# 04_Sensor.net
KiCad netlist of a schematic drawn in Altium Designer
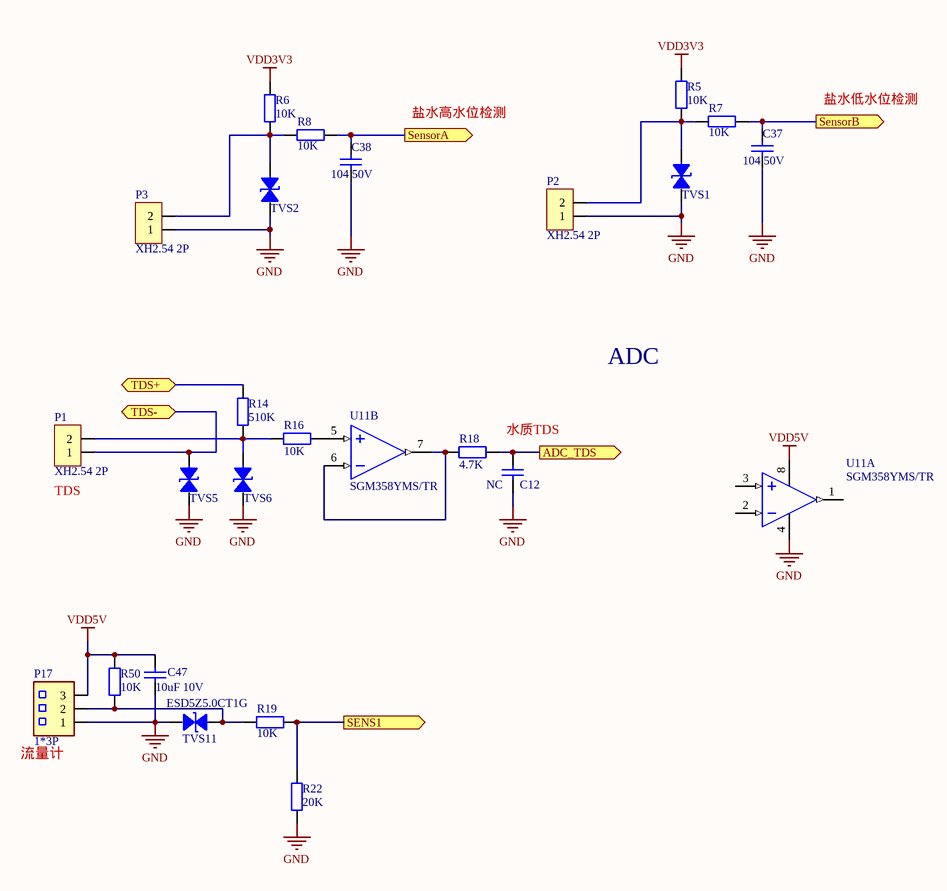
[diagram p0: 04_Sensor.SchDoc]

(export (version "E")
  (design (tool "Eeschema 10.0.6"))
  (components
    (comp (ref "C12")
      (value "NC")
      (footprint "SMD-0603C")
      (description "贴片电容 10%")
      (libsource (lib "XiaoyI") (part "CAP4"))
    )
    (comp (ref "C37")
      (value "104 50V")
      (footprint "SMD-0603C")
      (description "贴片电容 20%")
      (libsource (lib "XiaoyI") (part "CAP4"))
    )
    (comp (ref "C38")
      (value "104 50V")
      (footprint "SMD-0603C")
      (description "贴片电容 20%")
      (libsource (lib "XiaoyI") (part "CAP4"))
    )
    (comp (ref "C47")
      (value "10uF 10V")
      (footprint "SMD-0603C")
      (description "贴片电容 10%")
      (libsource (lib "Miscellaneous Devices LC") (part "0805 22uF (226) 20% 25V"))
    )
    (comp (ref "P1")
      (value "XH2.54 2P")
      (footprint "SIP-2A")
      (description "XH2.54 2P 直插")
      (libsource (lib "XiaoyI") (part "SIP-2"))
    )
    (comp (ref "P2")
      (value "XH2.54 2P")
      (footprint "SIP-2A")
      (description "XH2.54 2P 直插")
      (libsource (lib "XiaoyI") (part "SIP-2"))
    )
    (comp (ref "P3")
      (value "XH2.54 2P")
      (footprint "SIP-2A")
      (description "XH2.54 2P 直插")
      (libsource (lib "XiaoyI") (part "SIP-2"))
    )
    (comp (ref "P17")
      (value "1*3P")
      (footprint "3X2.54MMZ2")
      (libsource (lib "PARK-N5 V1.0") (part "HDR1*3"))
    )
    (comp (ref "R5")
      (value "10K")
      (footprint "SMD-0603")
      (description "贴片电阻 1%")
      (libsource (lib "ABB") (part "RES0"))
    )
    (comp (ref "R6")
      (value "10K")
      (footprint "SMD-0603")
      (description "贴片电阻 1%")
      (libsource (lib "ABB") (part "RES0"))
    )
    (comp (ref "R7")
      (value "10K")
      (footprint "SMD-0603")
      (description "贴片电阻 1%")
      (libsource (lib "") (part "RES0_2"))
    )
    (comp (ref "R8")
      (value "10K")
      (footprint "SMD-0603")
      (description "贴片电阻 1%")
      (libsource (lib "") (part "RES0_2"))
    )
    (comp (ref "R14")
      (value "510K")
      (footprint "SMD-0603")
      (description "贴片电阻 1%")
      (libsource (lib "ABB") (part "RES0"))
    )
    (comp (ref "R16")
      (value "10K")
      (footprint "SMD-0603")
      (description "贴片电阻 1%")
      (libsource (lib "") (part "RES0_2"))
    )
    (comp (ref "R18")
      (value "4.7K")
      (footprint "SMD-0603")
      (description "贴片电阻 5%")
      (libsource (lib "") (part "RES0_1"))
    )
    (comp (ref "R19")
      (value "10K")
      (footprint "SMD-0603")
      (description "贴片电阻 5%")
      (libsource (lib "Miscellaneous Devices LC") (part "0603 10KΩ (1002) 1%"))
    )
    (comp (ref "R22")
      (value "20K")
      (footprint "SMD-0603")
      (description "贴片电阻 5%")
      (libsource (lib "") (part "0603 10KΩ (1002) 1%_2"))
    )
    (comp (ref "R50")
      (value "10K")
      (footprint "SMD-0603")
      (description "贴片电阻 5%")
      (libsource (lib "") (part "0603 10KΩ (1002) 1%_1"))
    )
    (comp (ref "TVS1")
      (value "ESD5Z5.0CT1G")
      (footprint "SOD-523")
      (description "TVS")
      (libsource (lib "XiaoyI") (part "TVS-1"))
    )
    (comp (ref "TVS2")
      (value "ESD5Z5.0CT1G")
      (footprint "SOD-523")
      (description "TVS")
      (libsource (lib "XiaoyI") (part "TVS-1"))
    )
    (comp (ref "TVS5")
      (value "ESD5Z5.0CT1G")
      (footprint "SOD-523")
      (description "TVS")
      (libsource (lib "XiaoyI") (part "TVS-1"))
    )
    (comp (ref "TVS6")
      (value "ESD5Z5.0CT1G")
      (footprint "SOD-523")
      (description "TVS")
      (libsource (lib "XiaoyI") (part "TVS-1"))
    )
    (comp (ref "TVS11")
      (value "ESD5Z5.0CT1G")
      (footprint "SOD-523")
      (description "TVS 5.0V")
      (libsource (lib "XiaoyI") (part "TVS-1"))
    )
    (comp (ref "U11")
      (value "SGM358YMS/TR")
      (footprint "MSOP-8")
      (description "运放")
      (libsource (lib "XiaoyI") (part "LM358"))
    )
  )
  (nets
    (net (code "1") (name "/ADC_TDS") (class "Default")
      (node (ref "C12") (pin "2") (pinfunction "2_2") (pintype "passive"))
      (node (ref "R18") (pin "1") (pinfunction "1_1") (pintype "passive"))
    )
    (net (code "2") (name "/SENS1") (class "Default")
      (node (ref "R19") (pin "2") (pinfunction "2_2") (pintype "passive"))
      (node (ref "R22") (pin "2") (pinfunction "2_2") (pintype "passive"))
    )
    (net (code "3") (name "/SensorA") (class "Default")
      (node (ref "C38") (pin "2") (pinfunction "2_2") (pintype "passive"))
      (node (ref "R8") (pin "2") (pinfunction "2_2") (pintype "passive"))
    )
    (net (code "4") (name "/SensorB") (class "Default")
      (node (ref "C37") (pin "2") (pinfunction "2_2") (pintype "passive"))
      (node (ref "R7") (pin "2") (pinfunction "2_2") (pintype "passive"))
    )
    (net (code "5") (name "/TDS+") (class "Default")
      (node (ref "R14") (pin "1") (pinfunction "1_1") (pintype "passive"))
    )
    (net (code "6") (name "/TDS-") (class "Default")
      (node (ref "P1") (pin "1") (pinfunction "1_1") (pintype "passive"))
      (node (ref "TVS5") (pin "2") (pinfunction "B_2") (pintype "passive"))
    )
    (net (code "7") (name "GND") (class "Default")
      (node (ref "C12") (pin "1") (pinfunction "1_1") (pintype "passive"))
      (node (ref "C37") (pin "1") (pinfunction "1_1") (pintype "passive"))
      (node (ref "C38") (pin "1") (pinfunction "1_1") (pintype "passive"))
      (node (ref "C47") (pin "1") (pinfunction "1_1") (pintype "passive"))
      (node (ref "P17") (pin "1") (pinfunction "1_1") (pintype "passive"))
      (node (ref "P2") (pin "1") (pinfunction "1_1") (pintype "passive"))
      (node (ref "P3") (pin "1") (pinfunction "1_1") (pintype "passive"))
      (node (ref "R22") (pin "1") (pinfunction "1_1") (pintype "passive"))
      (node (ref "TVS1") (pin "1") (pinfunction "A_1") (pintype "passive"))
      (node (ref "TVS11") (pin "1") (pinfunction "A_1") (pintype "passive"))
      (node (ref "TVS2") (pin "1") (pinfunction "A_1") (pintype "passive"))
      (node (ref "TVS5") (pin "1") (pinfunction "A_1") (pintype "passive"))
      (node (ref "TVS6") (pin "1") (pinfunction "A_1") (pintype "passive"))
      (node (ref "U11") (pin "4") (pinfunction "V-_4") (pintype "power_in"))
    )
    (net (code "8") (name "Net-(TVS1-B)") (class "Default")
      (node (ref "P2") (pin "2") (pinfunction "2_2") (pintype "passive"))
      (node (ref "R5") (pin "2") (pinfunction "2_2") (pintype "passive"))
      (node (ref "R7") (pin "1") (pinfunction "1_1") (pintype "passive"))
      (node (ref "TVS1") (pin "2") (pinfunction "B_2") (pintype "passive"))
    )
    (net (code "9") (name "Net-(TVS2-B)") (class "Default")
      (node (ref "P3") (pin "2") (pinfunction "2_2") (pintype "passive"))
      (node (ref "R6") (pin "2") (pinfunction "2_2") (pintype "passive"))
      (node (ref "R8") (pin "1") (pinfunction "1_1") (pintype "passive"))
      (node (ref "TVS2") (pin "2") (pinfunction "B_2") (pintype "passive"))
    )
    (net (code "10") (name "Net-(TVS6-B)") (class "Default")
      (node (ref "P1") (pin "2") (pinfunction "2_2") (pintype "passive"))
      (node (ref "R14") (pin "2") (pinfunction "2_2") (pintype "passive"))
      (node (ref "R16") (pin "1") (pinfunction "1_1") (pintype "passive"))
      (node (ref "TVS6") (pin "2") (pinfunction "B_2") (pintype "passive"))
    )
    (net (code "11") (name "Net-(TVS11-B)") (class "Default")
      (node (ref "P17") (pin "2") (pinfunction "2_2") (pintype "passive"))
      (node (ref "R19") (pin "1") (pinfunction "1_1") (pintype "passive"))
      (node (ref "R50") (pin "2") (pinfunction "2_2") (pintype "passive"))
      (node (ref "TVS11") (pin "2") (pinfunction "B_2") (pintype "passive"))
    )
    (net (code "12") (name "Net-(U11B-IN2+)") (class "Default")
      (node (ref "R16") (pin "2") (pinfunction "2_2") (pintype "passive"))
      (node (ref "U11") (pin "5") (pinfunction "IN2+_5") (pintype "input"))
    )
    (net (code "13") (name "Net-(U11B-IN2-)") (class "Default")
      (node (ref "R18") (pin "2") (pinfunction "2_2") (pintype "passive"))
      (node (ref "U11") (pin "6") (pinfunction "IN2-_6") (pintype "input"))
      (node (ref "U11") (pin "7") (pinfunction "OUT2_7") (pintype "output"))
    )
    (net (code "14") (name "VDD3V3") (class "Default")
      (node (ref "R5") (pin "1") (pinfunction "1_1") (pintype "passive"))
      (node (ref "R6") (pin "1") (pinfunction "1_1") (pintype "passive"))
    )
    (net (code "15") (name "VDD5V") (class "Default")
      (node (ref "C47") (pin "2") (pinfunction "2_2") (pintype "passive"))
      (node (ref "P17") (pin "3") (pinfunction "3_3") (pintype "passive"))
      (node (ref "R50") (pin "1") (pinfunction "1_1") (pintype "passive"))
      (node (ref "U11") (pin "8") (pinfunction "V+_8") (pintype "power_in"))
    )
    (net (code "16") (name "unconnected-(U11A-IN1+-Pad3)") (class "Default")
      (node (ref "U11") (pin "3") (pinfunction "IN1+_3") (pintype "input"))
    )
    (net (code "17") (name "unconnected-(U11A-IN1--Pad2)") (class "Default")
      (node (ref "U11") (pin "2") (pinfunction "IN1-_2") (pintype "input"))
    )
    (net (code "18") (name "unconnected-(U11A-OUT1-Pad1)") (class "Default")
      (node (ref "U11") (pin "1") (pinfunction "OUT1_1") (pintype "output"))
    )
  )
)
